# gunes_paneli.net
KiCad netlist of a schematic drawn in EAGLE
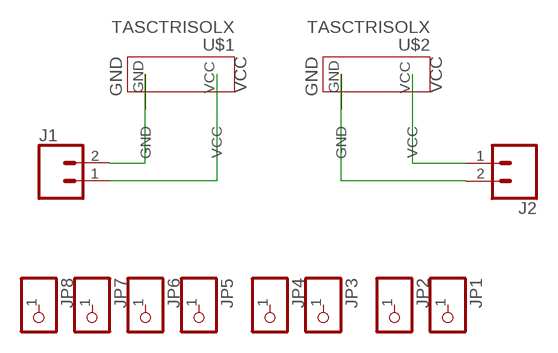
[diagram p0: schematic, sheet 1]

(export (version "E")
  (design (tool "Eeschema 10.0.6"))
  (components
    (comp (ref "J1")
      (value "CONN_02")
      (footprint "eagle-import:1X02")
      (libsource (lib "eagle-import") (part "CONN_02"))
    )
    (comp (ref "J2")
      (value "CONN_02")
      (footprint "eagle-import:1X02")
      (libsource (lib "eagle-import") (part "CONN_02"))
    )
    (comp (ref "JP1")
      (value "PINHD-1X1CB")
      (footprint "eagle-import:1X01-CLEANBIG")
      (libsource (lib "eagle-import") (part "PINHD-1X1CB"))
    )
    (comp (ref "JP2")
      (value "PINHD-1X1CB")
      (footprint "eagle-import:1X01-CLEANBIG")
      (libsource (lib "eagle-import") (part "PINHD-1X1CB"))
    )
    (comp (ref "JP3")
      (value "PINHD-1X1CB")
      (footprint "eagle-import:1X01-CLEANBIG")
      (libsource (lib "eagle-import") (part "PINHD-1X1CB"))
    )
    (comp (ref "JP4")
      (value "PINHD-1X1CB")
      (footprint "eagle-import:1X01-CLEANBIG")
      (libsource (lib "eagle-import") (part "PINHD-1X1CB"))
    )
    (comp (ref "JP5")
      (value "PINHD-1X1CB")
      (footprint "eagle-import:1X01-CLEANBIG")
      (libsource (lib "eagle-import") (part "PINHD-1X1CB"))
    )
    (comp (ref "JP6")
      (value "PINHD-1X1CB")
      (footprint "eagle-import:1X01-CLEANBIG")
      (libsource (lib "eagle-import") (part "PINHD-1X1CB"))
    )
    (comp (ref "JP7")
      (value "PINHD-1X1CB")
      (footprint "eagle-import:1X01-CLEANBIG")
      (libsource (lib "eagle-import") (part "PINHD-1X1CB"))
    )
    (comp (ref "JP8")
      (value "PINHD-1X1CB")
      (footprint "eagle-import:1X01-CLEANBIG")
      (libsource (lib "eagle-import") (part "PINHD-1X1CB"))
    )
    (comp (ref "U$1")
      (value "TASCTRISOLX")
      (footprint "eagle-import:TASCTRİSOLX")
      (libsource (lib "eagle-import") (part "TASCTRISOLX"))
    )
    (comp (ref "U$2")
      (value "TASCTRISOLX")
      (footprint "eagle-import:TASCTRİSOLX")
      (libsource (lib "eagle-import") (part "TASCTRISOLX"))
    )
  )
  (nets
    (net (code "1") (name "Net-(J1-Pad1)") (class "Default")
      (node (ref "J1") (pin "1") (pinfunction "1_1") (pintype "passive"))
      (node (ref "U$1") (pin "VCC") (pinfunction "VCC_VCC") (pintype "bidirectional"))
    )
    (net (code "2") (name "Net-(J1-Pad2)") (class "Default")
      (node (ref "J1") (pin "2") (pinfunction "2_2") (pintype "passive"))
      (node (ref "U$1") (pin "GND") (pinfunction "GND_GND") (pintype "bidirectional"))
    )
    (net (code "3") (name "Net-(J2-Pad1)") (class "Default")
      (node (ref "J2") (pin "1") (pinfunction "1_1") (pintype "passive"))
      (node (ref "U$2") (pin "VCC") (pinfunction "VCC_VCC") (pintype "bidirectional"))
    )
    (net (code "4") (name "Net-(J2-Pad2)") (class "Default")
      (node (ref "J2") (pin "2") (pinfunction "2_2") (pintype "passive"))
      (node (ref "U$2") (pin "GND") (pinfunction "GND_GND") (pintype "bidirectional"))
    )
    (net (code "5") (name "unconnected-(JP1-Pad1)") (class "Default")
      (node (ref "JP1") (pin "1") (pinfunction "1_1") (pintype "passive"))
    )
    (net (code "6") (name "unconnected-(JP2-Pad1)") (class "Default")
      (node (ref "JP2") (pin "1") (pinfunction "1_1") (pintype "passive"))
    )
    (net (code "7") (name "unconnected-(JP3-Pad1)") (class "Default")
      (node (ref "JP3") (pin "1") (pinfunction "1_1") (pintype "passive"))
    )
    (net (code "8") (name "unconnected-(JP4-Pad1)") (class "Default")
      (node (ref "JP4") (pin "1") (pinfunction "1_1") (pintype "passive"))
    )
    (net (code "9") (name "unconnected-(JP5-Pad1)") (class "Default")
      (node (ref "JP5") (pin "1") (pinfunction "1_1") (pintype "passive"))
    )
    (net (code "10") (name "unconnected-(JP6-Pad1)") (class "Default")
      (node (ref "JP6") (pin "1") (pinfunction "1_1") (pintype "passive"))
    )
    (net (code "11") (name "unconnected-(JP7-Pad1)") (class "Default")
      (node (ref "JP7") (pin "1") (pinfunction "1_1") (pintype "passive"))
    )
    (net (code "12") (name "unconnected-(JP8-Pad1)") (class "Default")
      (node (ref "JP8") (pin "1") (pinfunction "1_1") (pintype "passive"))
    )
  )
)
